# HP_Delta_DPS-600WB_A.net
KiCad netlist of a schematic drawn in EAGLE
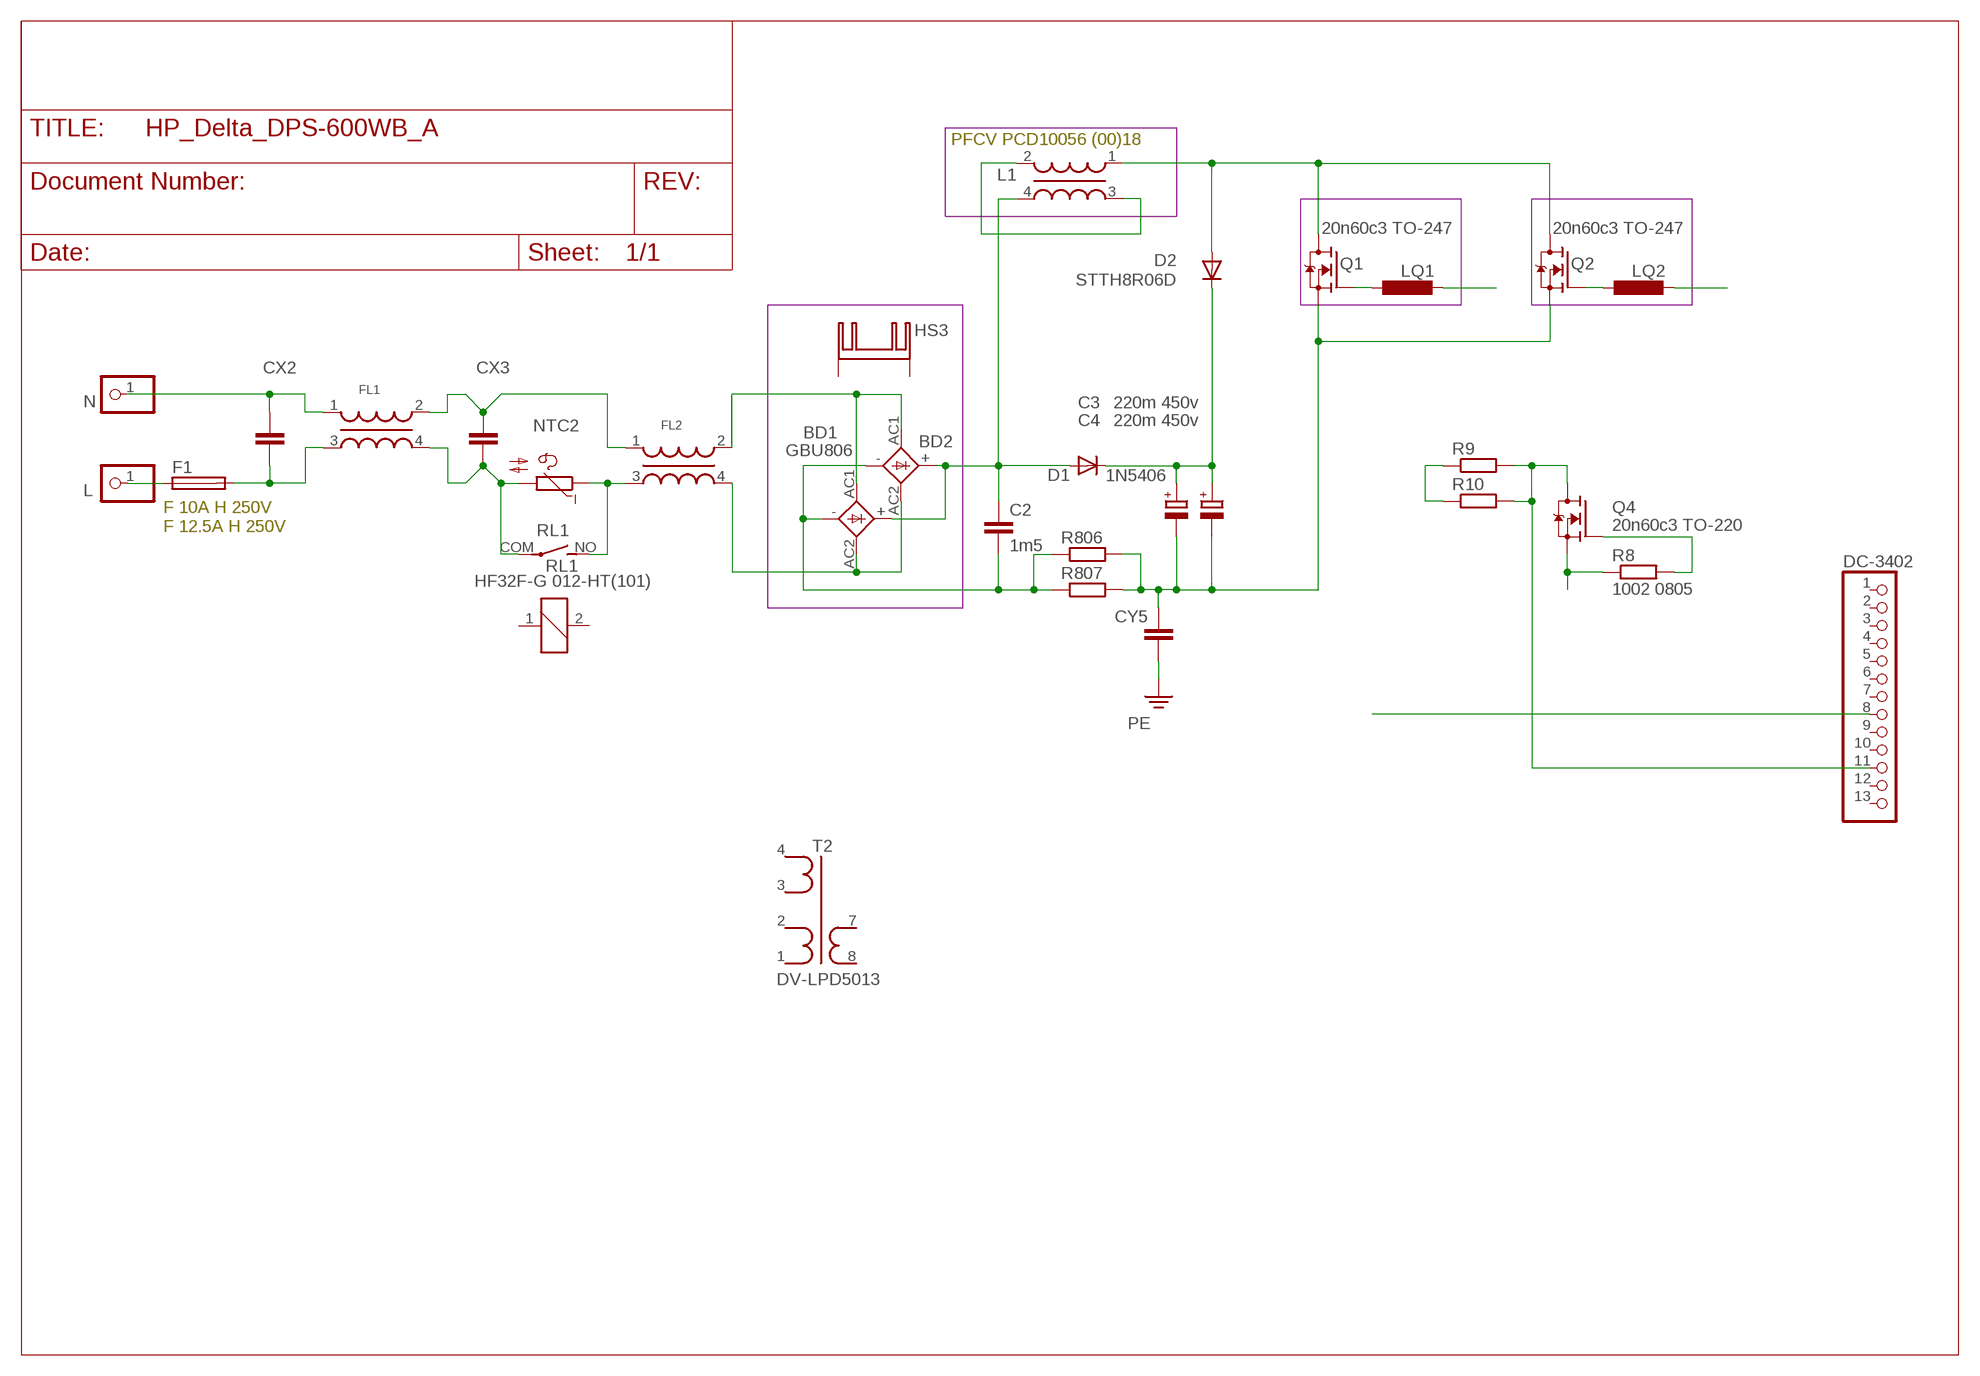
[diagram p0: schematic, sheet 1]

(export (version "E")
  (design (tool "Eeschema 10.0.6"))
  (components
    (comp (ref "BD1")
      (value "GBU806")
      (footprint "eagle-import:2KBB-R")
      (libsource (lib "eagle-import") (part "2KBB-R"))
    )
    (comp (ref "BD2")
      (value "2KBB-R")
      (footprint "eagle-import:2KBB-R")
      (libsource (lib "eagle-import") (part "2KBB-R"))
    )
    (comp (ref "C2")
      (value "1m5")
      (footprint "eagle-import:C150-072X183")
      (libsource (lib "eagle-import") (part "C-EU150-072X183"))
    )
    (comp (ref "C3")
      (value "220m 450v")
      (footprint "eagle-import:SANYO-OSCON_E7")
      (libsource (lib "eagle-import") (part "CPOL-EUSANYO_E7"))
    )
    (comp (ref "C4")
      (value "220m 450v")
      (footprint "eagle-import:SANYO-OSCON_E7")
      (libsource (lib "eagle-import") (part "CPOL-EUSANYO_E7"))
    )
    (comp (ref "CX2")
      (value "C-EU150-072X183")
      (footprint "eagle-import:C150-072X183")
      (libsource (lib "eagle-import") (part "C-EU150-072X183"))
    )
    (comp (ref "CX3")
      (value "C-EU150-072X183")
      (footprint "eagle-import:C150-072X183")
      (libsource (lib "eagle-import") (part "C-EU150-072X183"))
    )
    (comp (ref "CY5")
      (value "C-EU025-040X050")
      (footprint "eagle-import:C025-040X050")
      (libsource (lib "eagle-import") (part "C-EU025-040X050"))
    )
    (comp (ref "D1")
      (value "1N5406")
      (footprint "eagle-import:DO41-10")
      (libsource (lib "eagle-import") (part "1N4942"))
    )
    (comp (ref "D2")
      (value "STTH8R06D")
      (footprint "eagle-import:DO220S")
      (libsource (lib "eagle-import") (part "BYT85"))
    )
    (comp (ref "DC-3402")
      (value "PINHD-1X13")
      (footprint "eagle-import:1X13")
      (libsource (lib "eagle-import") (part "PINHD-1X13"))
    )
    (comp (ref "F1")
      (value "19560")
      (footprint "eagle-import:19560")
      (fields (field (name "MPN") "56000001009"))
      (libsource (lib "eagle-import") (part "19560"))
    )
    (comp (ref "FL1")
      (value "LFLF-10X13")
      (footprint "eagle-import:LF-10X13")
      (libsource (lib "eagle-import") (part "LFLF-10X13"))
    )
    (comp (ref "FL2")
      (value "LFLF-10X13")
      (footprint "eagle-import:LF-10X13")
      (libsource (lib "eagle-import") (part "LFLF-10X13"))
    )
    (comp (ref "HS3")
      (value "FK222")
      (footprint "eagle-import:FK222")
      (libsource (lib "eagle-import") (part "FK222"))
    )
    (comp (ref "L")
      (value "PINHD-1X1")
      (footprint "eagle-import:1X01")
      (libsource (lib "eagle-import") (part "PINHD-1X1"))
    )
    (comp (ref "L1")
      (value "PFCV PCD10056 (00)18")
      (footprint "eagle-import:LF-10X13")
      (libsource (lib "eagle-import") (part "LFLF-10X13"))
    )
    (comp (ref "LQ1")
      (value "L-EU0204/5")
      (footprint "eagle-import:0204_5")
      (libsource (lib "eagle-import") (part "L-EU0204/5"))
    )
    (comp (ref "LQ2")
      (value "L-EU0204/5")
      (footprint "eagle-import:0204_5")
      (libsource (lib "eagle-import") (part "L-EU0204/5"))
    )
    (comp (ref "N")
      (value "PINHD-1X1")
      (footprint "eagle-import:1X01")
      (libsource (lib "eagle-import") (part "PINHD-1X1"))
    )
    (comp (ref "NTC2")
      (value "B57164")
      (footprint "eagle-import:B57164")
      (fields (field (name "MPN") "B57164K474K52"))
      (libsource (lib "eagle-import") (part "B57164"))
    )
    (comp (ref "Q1")
      (value "20n60c3 TO-247")
      (footprint "eagle-import:P-TO247")
      (libsource (lib "eagle-import") (part "SPW47N60S5"))
    )
    (comp (ref "Q2")
      (value "20n60c3 TO-247")
      (footprint "eagle-import:P-TO247")
      (libsource (lib "eagle-import") (part "SPW47N60S5"))
    )
    (comp (ref "Q4")
      (value "20n60c3 TO-220")
      (footprint "eagle-import:P-TO247")
      (libsource (lib "eagle-import") (part "SPW47N60S5"))
    )
    (comp (ref "R8")
      (value "1002 0805")
      (footprint "eagle-import:R0805")
      (libsource (lib "eagle-import") (part "R-EU_R0805"))
    )
    (comp (ref "R9")
      (value "R-EU_0204/7")
      (footprint "eagle-import:0204_7")
      (libsource (lib "eagle-import") (part "R-EU_0204/7"))
    )
    (comp (ref "R10")
      (value "R-EU_0204/7")
      (footprint "eagle-import:0204_7")
      (libsource (lib "eagle-import") (part "R-EU_0204/7"))
    )
    (comp (ref "R806")
      (value "R-EU_0309/12")
      (footprint "eagle-import:0309_12")
      (libsource (lib "eagle-import") (part "R-EU_0309/12"))
    )
    (comp (ref "R807")
      (value "R-EU_0309/12")
      (footprint "eagle-import:0309_12")
      (libsource (lib "eagle-import") (part "R-EU_0309/12"))
    )
    (comp (ref "RL1")
      (value "HF32F-G 012-HT(101)")
      (footprint "eagle-import:APF30212A")
      (libsource (lib "eagle-import") (part "APF30212A"))
    )
    (comp (ref "T2")
      (value "DV-LPD5013")
      (footprint "eagle-import:DV-LPD5013")
      (libsource (lib "eagle-import") (part "DV-LPD5013"))
    )
  )
  (nets
    (net (code "1") (name "Net-(BD1-Pad+)") (class "Default")
      (node (ref "BD1") (pin "+") (pinfunction "+_+") (pintype "passive"))
      (node (ref "BD2") (pin "+") (pinfunction "+_+") (pintype "passive"))
      (node (ref "C2") (pin "1") (pinfunction "1_1") (pintype "passive"))
      (node (ref "D1") (pin "A") (pinfunction "A_A") (pintype "passive"))
      (node (ref "L1") (pin "4") (pinfunction "4_4") (pintype "bidirectional"))
    )
    (net (code "2") (name "Net-(BD1-Pad-)") (class "Default")
      (node (ref "BD1") (pin "-") (pinfunction "-_-") (pintype "passive"))
      (node (ref "BD2") (pin "-") (pinfunction "-_-") (pintype "passive"))
      (node (ref "C2") (pin "2") (pinfunction "2_2") (pintype "passive"))
      (node (ref "R806") (pin "1") (pinfunction "1_1") (pintype "passive"))
      (node (ref "R807") (pin "1") (pinfunction "1_1") (pintype "passive"))
    )
    (net (code "3") (name "Net-(BD1-PadAC1)") (class "Default")
      (node (ref "BD1") (pin "AC1") (pinfunction "AC1_AC1") (pintype "passive"))
      (node (ref "BD2") (pin "AC1") (pinfunction "AC1_AC1") (pintype "passive"))
      (node (ref "FL2") (pin "2") (pinfunction "2_2") (pintype "bidirectional"))
    )
    (net (code "4") (name "Net-(BD1-PadAC2)") (class "Default")
      (node (ref "BD1") (pin "AC2") (pinfunction "AC2_AC2") (pintype "passive"))
      (node (ref "BD2") (pin "AC2") (pinfunction "AC2_AC2") (pintype "passive"))
      (node (ref "FL2") (pin "4") (pinfunction "4_4") (pintype "bidirectional"))
    )
    (net (code "5") (name "Net-(C3-Pad+)") (class "Default")
      (node (ref "C3") (pin "+") (pinfunction "+_+") (pintype "passive"))
      (node (ref "C4") (pin "+") (pinfunction "+_+") (pintype "passive"))
      (node (ref "D1") (pin "C") (pinfunction "C_C") (pintype "passive"))
      (node (ref "D2") (pin "C") (pinfunction "C_C") (pintype "passive"))
    )
    (net (code "6") (name "Net-(CX2-Pad1)") (class "Default")
      (node (ref "CX2") (pin "1") (pinfunction "1_1") (pintype "passive"))
      (node (ref "FL1") (pin "1") (pinfunction "1_1") (pintype "bidirectional"))
      (node (ref "N") (pin "1") (pinfunction "1_1") (pintype "passive"))
    )
    (net (code "7") (name "Net-(CX2-Pad2)") (class "Default")
      (node (ref "CX2") (pin "2") (pinfunction "2_2") (pintype "passive"))
      (node (ref "F1") (pin "2") (pinfunction "2_2") (pintype "passive"))
      (node (ref "FL1") (pin "3") (pinfunction "3_3") (pintype "bidirectional"))
    )
    (net (code "8") (name "Net-(CX3-Pad1)") (class "Default")
      (node (ref "CX3") (pin "1") (pinfunction "1_1") (pintype "passive"))
      (node (ref "FL1") (pin "2") (pinfunction "2_2") (pintype "bidirectional"))
      (node (ref "FL2") (pin "1") (pinfunction "1_1") (pintype "bidirectional"))
    )
    (net (code "9") (name "Net-(F1-Pad1)") (class "Default")
      (node (ref "F1") (pin "1") (pinfunction "1_1") (pintype "passive"))
      (node (ref "L") (pin "1") (pinfunction "1_1") (pintype "passive"))
    )
    (net (code "10") (name "Net-(L1-Pad2)") (class "Default")
      (node (ref "L1") (pin "2") (pinfunction "2_2") (pintype "bidirectional"))
      (node (ref "L1") (pin "3") (pinfunction "3_3") (pintype "bidirectional"))
    )
    (net (code "11") (name "Net-(Q1-D)") (class "Default")
      (node (ref "D2") (pin "A") (pinfunction "A_A") (pintype "passive"))
      (node (ref "L1") (pin "1") (pinfunction "1_1") (pintype "bidirectional"))
      (node (ref "Q1") (pin "2") (pinfunction "D_2") (pintype "passive"))
      (node (ref "Q2") (pin "2") (pinfunction "D_2") (pintype "passive"))
    )
    (net (code "12") (name "Net-(Q1-G)") (class "Default")
      (node (ref "LQ1") (pin "1") (pinfunction "1_1") (pintype "passive"))
      (node (ref "Q1") (pin "1") (pinfunction "G_1") (pintype "passive"))
    )
    (net (code "13") (name "Net-(Q1-S)") (class "Default")
      (node (ref "C3") (pin "-") (pinfunction "-_-") (pintype "passive"))
      (node (ref "C4") (pin "-") (pinfunction "-_-") (pintype "passive"))
      (node (ref "CY5") (pin "1") (pinfunction "1_1") (pintype "passive"))
      (node (ref "Q1") (pin "3") (pinfunction "S_3") (pintype "passive"))
      (node (ref "Q2") (pin "3") (pinfunction "S_3") (pintype "passive"))
      (node (ref "R806") (pin "2") (pinfunction "2_2") (pintype "passive"))
      (node (ref "R807") (pin "2") (pinfunction "2_2") (pintype "passive"))
    )
    (net (code "14") (name "Net-(Q2-G)") (class "Default")
      (node (ref "LQ2") (pin "1") (pinfunction "1_1") (pintype "passive"))
      (node (ref "Q2") (pin "1") (pinfunction "G_1") (pintype "passive"))
    )
    (net (code "15") (name "Net-(Q4-D)") (class "Default")
      (node (ref "DC-3402") (pin "11") (pinfunction "11_11") (pintype "passive"))
      (node (ref "Q4") (pin "2") (pinfunction "D_2") (pintype "passive"))
      (node (ref "R10") (pin "2") (pinfunction "2_2") (pintype "passive"))
      (node (ref "R9") (pin "2") (pinfunction "2_2") (pintype "passive"))
    )
    (net (code "16") (name "Net-(Q4-G)") (class "Default")
      (node (ref "Q4") (pin "1") (pinfunction "G_1") (pintype "passive"))
      (node (ref "R8") (pin "2") (pinfunction "2_2") (pintype "passive"))
    )
    (net (code "17") (name "Net-(Q4-S)") (class "Default")
      (node (ref "Q4") (pin "3") (pinfunction "S_3") (pintype "passive"))
      (node (ref "R8") (pin "1") (pinfunction "1_1") (pintype "passive"))
    )
    (net (code "18") (name "Net-(R10-Pad1)") (class "Default")
      (node (ref "R10") (pin "1") (pinfunction "1_1") (pintype "passive"))
      (node (ref "R9") (pin "1") (pinfunction "1_1") (pintype "passive"))
    )
    (net (code "19") (name "Net-(RL1B-P)") (class "Default")
      (node (ref "CX3") (pin "2") (pinfunction "2_2") (pintype "passive"))
      (node (ref "FL1") (pin "4") (pinfunction "4_4") (pintype "bidirectional"))
      (node (ref "NTC2") (pin "2") (pinfunction "2_2") (pintype "passive"))
      (node (ref "RL1") (pin "COM") (pinfunction "P_COM") (pintype "passive"))
    )
    (net (code "20") (name "Net-(RL1B-S)") (class "Default")
      (node (ref "FL2") (pin "3") (pinfunction "3_3") (pintype "bidirectional"))
      (node (ref "NTC2") (pin "1") (pinfunction "1_1") (pintype "passive"))
      (node (ref "RL1") (pin "NO") (pinfunction "S_NO") (pintype "passive"))
    )
    (net (code "21") (name "PE") (class "Default")
      (node (ref "CY5") (pin "2") (pinfunction "2_2") (pintype "passive"))
    )
    (net (code "22") (name "unconnected-(DC-3402-Pad1)") (class "Default")
      (node (ref "DC-3402") (pin "1") (pinfunction "1_1") (pintype "passive"))
    )
    (net (code "23") (name "unconnected-(DC-3402-Pad2)") (class "Default")
      (node (ref "DC-3402") (pin "2") (pinfunction "2_2") (pintype "passive"))
    )
    (net (code "24") (name "unconnected-(DC-3402-Pad3)") (class "Default")
      (node (ref "DC-3402") (pin "3") (pinfunction "3_3") (pintype "passive"))
    )
    (net (code "25") (name "unconnected-(DC-3402-Pad4)") (class "Default")
      (node (ref "DC-3402") (pin "4") (pinfunction "4_4") (pintype "passive"))
    )
    (net (code "26") (name "unconnected-(DC-3402-Pad5)") (class "Default")
      (node (ref "DC-3402") (pin "5") (pinfunction "5_5") (pintype "passive"))
    )
    (net (code "27") (name "unconnected-(DC-3402-Pad6)") (class "Default")
      (node (ref "DC-3402") (pin "6") (pinfunction "6_6") (pintype "passive"))
    )
    (net (code "28") (name "unconnected-(DC-3402-Pad7)") (class "Default")
      (node (ref "DC-3402") (pin "7") (pinfunction "7_7") (pintype "passive"))
    )
    (net (code "29") (name "unconnected-(DC-3402-Pad8)") (class "Default")
      (node (ref "DC-3402") (pin "8") (pinfunction "8_8") (pintype "passive"))
    )
    (net (code "30") (name "unconnected-(DC-3402-Pad9)") (class "Default")
      (node (ref "DC-3402") (pin "9") (pinfunction "9_9") (pintype "passive"))
    )
    (net (code "31") (name "unconnected-(DC-3402-Pad10)") (class "Default")
      (node (ref "DC-3402") (pin "10") (pinfunction "10_10") (pintype "passive"))
    )
    (net (code "32") (name "unconnected-(DC-3402-Pad12)") (class "Default")
      (node (ref "DC-3402") (pin "12") (pinfunction "12_12") (pintype "passive"))
    )
    (net (code "33") (name "unconnected-(DC-3402-Pad13)") (class "Default")
      (node (ref "DC-3402") (pin "13") (pinfunction "13_13") (pintype "passive"))
    )
    (net (code "34") (name "unconnected-(HS3-K-PadA2,8)") (class "Default")
      (node (ref "HS3") (pin "A2,8") (pinfunction "K_A2,8") (pintype "passive"))
    )
    (net (code "35") (name "unconnected-(HS3-K-PadB2,8)") (class "Default")
      (node (ref "HS3") (pin "B2,8") (pinfunction "K_B2,8") (pintype "passive"))
    )
    (net (code "36") (name "unconnected-(LQ1-Pad2)") (class "Default")
      (node (ref "LQ1") (pin "2") (pinfunction "2_2") (pintype "passive"))
    )
    (net (code "37") (name "unconnected-(LQ2-Pad2)") (class "Default")
      (node (ref "LQ2") (pin "2") (pinfunction "2_2") (pintype "passive"))
    )
    (net (code "38") (name "unconnected-(RL1-Pad1)") (class "Default")
      (node (ref "RL1") (pin "1") (pinfunction "1_1") (pintype "passive"))
    )
    (net (code "39") (name "unconnected-(RL1-Pad2)") (class "Default")
      (node (ref "RL1") (pin "2") (pinfunction "2_2") (pintype "passive"))
    )
    (net (code "40") (name "unconnected-(T2-P$1-Pad1)") (class "Default")
      (node (ref "T2") (pin "1") (pinfunction "P$1_1") (pintype "bidirectional"))
    )
    (net (code "41") (name "unconnected-(T2-P$2-Pad2)") (class "Default")
      (node (ref "T2") (pin "2") (pinfunction "P$2_2") (pintype "bidirectional"))
    )
    (net (code "42") (name "unconnected-(T2-P$3-Pad3)") (class "Default")
      (node (ref "T2") (pin "3") (pinfunction "P$3_3") (pintype "bidirectional"))
    )
    (net (code "43") (name "unconnected-(T2-P$4-Pad4)") (class "Default")
      (node (ref "T2") (pin "4") (pinfunction "P$4_4") (pintype "bidirectional"))
    )
    (net (code "44") (name "unconnected-(T2-P$7-Pad7)") (class "Default")
      (node (ref "T2") (pin "7") (pinfunction "P$7_7") (pintype "bidirectional"))
    )
    (net (code "45") (name "unconnected-(T2-P$8-Pad8)") (class "Default")
      (node (ref "T2") (pin "8") (pinfunction "P$8_8") (pintype "bidirectional"))
    )
  )
)
